# UBC-Thunderbots_PCB_Power__archive_power.net
KiCad netlist of a schematic drawn in Altium Designer
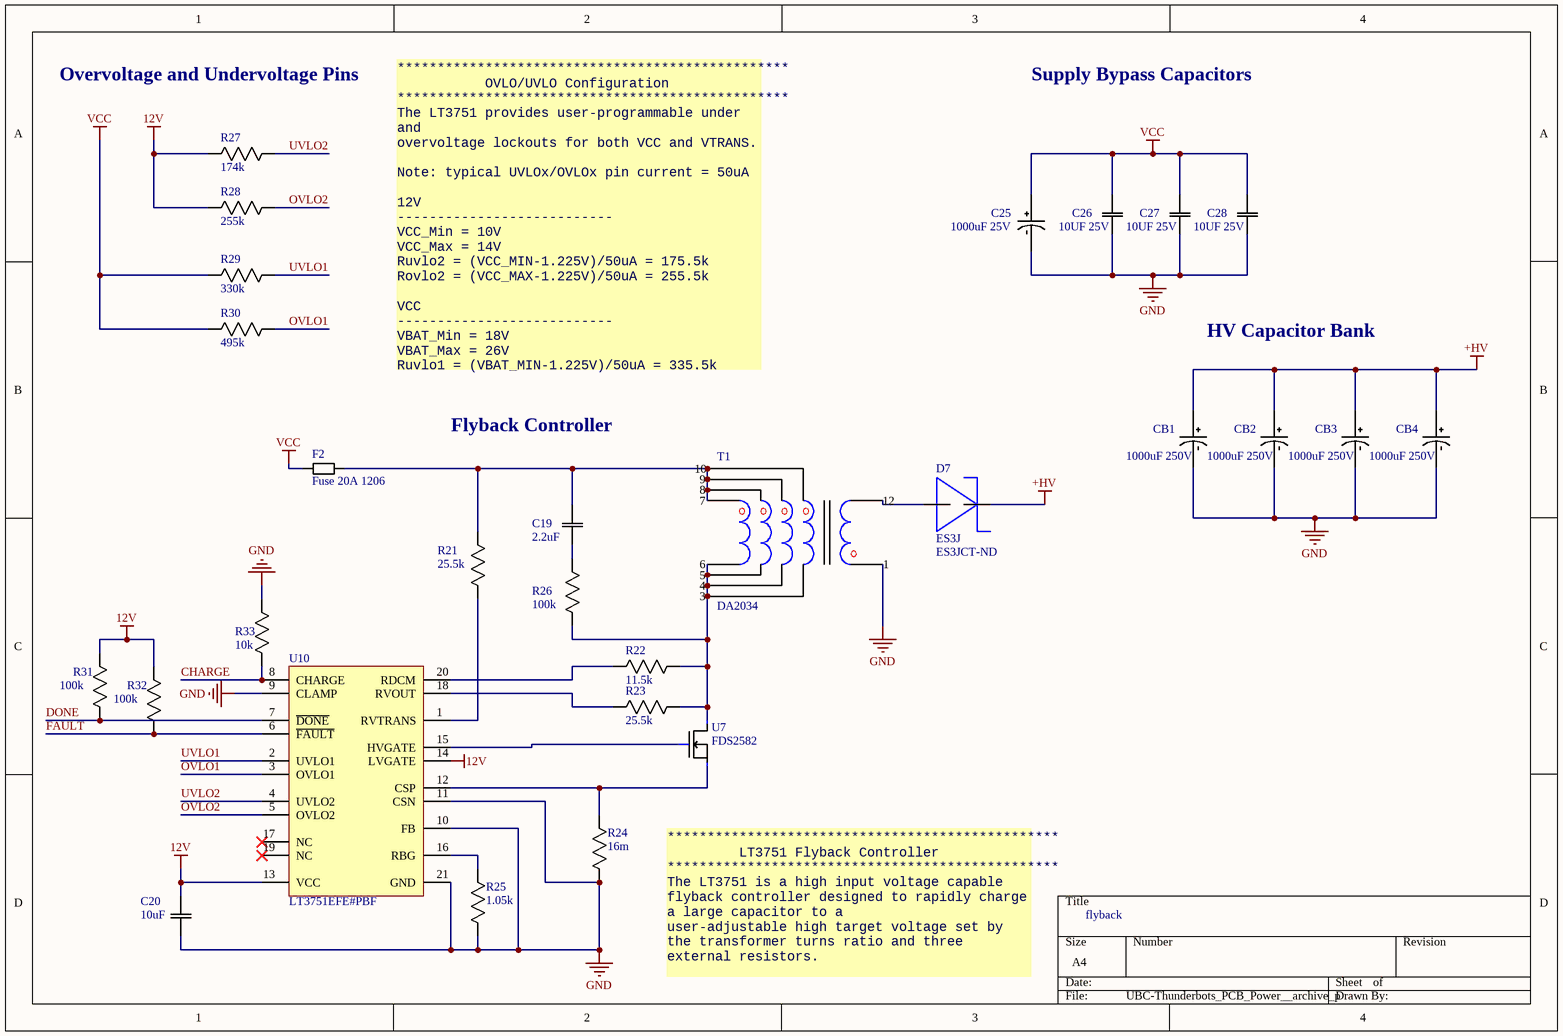
[diagram p0: UBC-Thunderbots_PCB_Power__archive_power-v2.2_pcb__flyback.SchDoc]

(export (version "E")
  (design (tool "Eeschema 10.0.6"))
  (components
    (comp (ref "C19")
      (value "2.2uF")
      (footprint "0805")
      (description "CAP CER 1UF 50V X7R 0805")
      (fields (field (name "MP") "C0805C225K4RACTU") (field (name "MF") "KEMET"))
      (libsource (lib "AltiumLibraries") (part "CAP 2.2uF 0805"))
    )
    (comp (ref "C20")
      (value "10uF")
      (footprint "0805")
      (description "CAP CER 10UF 10V X5R 0805")
      (fields (field (name "MP") "C0805C106K8PACTU") (field (name "MF") "KEMET"))
      (libsource (lib "AltiumLibraries") (part "CAP 10uF 0805"))
    )
    (comp (ref "C25")
      (value "1000uF 25V")
      (footprint "CAP POL 1000uF THRU")
      (description "NICHICON   UVR1E102MPD1TD   ALUMINUM ELECTROLYTIC CAPACITOR, 1000UF, 25V, 20%, RADIAL, FULL REEL")
      (fields
        (field (name "MANUFACTURER") "Nichicon")
        (field (name "MANUFACTURER PART NUMBER") "UVR1E102MPD1TD")
      )
      (libsource (lib "AltiumLibraries") (part "CAP POL 1000uF THRU"))
    )
    (comp (ref "C26")
      (value "10UF 25V")
      (footprint "1206")
      (description "CAP CER 10UF 25V X5R 1206")
      (fields (field (name "TOLERANCE") "10%"))
      (libsource (lib "") (part "CAP 10uF 25V_1"))
    )
    (comp (ref "C27")
      (value "10UF 25V")
      (footprint "1206")
      (description "CAP CER 10UF 25V X5R 1206")
      (fields (field (name "TOLERANCE") "10%"))
      (libsource (lib "AltiumLibraries") (part "CAP 10uF 25V"))
    )
    (comp (ref "C28")
      (value "10UF 25V")
      (footprint "1206")
      (description "CAP CER 10UF 25V X5R 1206")
      (fields (field (name "TOLERANCE") "10%"))
      (libsource (lib "AltiumLibraries") (part "CAP 10uF 25V"))
    )
    (comp (ref "CB1")
      (value "1000uF 250V")
      (description "1000µF 250V Aluminum Electrolytic Capacitors Radial, Can - Snap-In  3000 Hrs @ 85°C")
      (fields (field (name "TOLERANCE") "20%"))
      (libsource (lib "AltiumLibraries") (part "CAP ALUM 1000UF 20% 250V SNAP"))
    )
    (comp (ref "CB2")
      (value "1000uF 250V")
      (description "1000µF 250V Aluminum Electrolytic Capacitors Radial, Can - Snap-In  3000 Hrs @ 85°C")
      (fields (field (name "TOLERANCE") "20%"))
      (libsource (lib "AltiumLibraries") (part "CAP ALUM 1000UF 20% 250V SNAP"))
    )
    (comp (ref "CB3")
      (value "1000uF 250V")
      (description "1000µF 250V Aluminum Electrolytic Capacitors Radial, Can - Snap-In  3000 Hrs @ 85°C")
      (fields (field (name "TOLERANCE") "20%"))
      (libsource (lib "AltiumLibraries") (part "CAP ALUM 1000UF 20% 250V SNAP"))
    )
    (comp (ref "CB4")
      (value "1000uF 250V")
      (description "1000µF 250V Aluminum Electrolytic Capacitors Radial, Can - Snap-In  3000 Hrs @ 85°C")
      (fields (field (name "TOLERANCE") "20%"))
      (libsource (lib "AltiumLibraries") (part "CAP ALUM 1000UF 20% 250V SNAP"))
    )
    (comp (ref "D7")
      (value "ES3J")
      (footprint "D0214-AB")
      (description "Diode Switching 600V 3A 2-Pin DO-214AB T/R")
      (fields
        (field (name "MANUFACTURER") "ON Semiconductor / Fairchild")
        (field (name "VOLTAGE") "600V")
        (field (name "SUPPLIER PART NUMBER 1") "ES3JCT-ND")
      )
      (libsource (lib "AltiumLibraries") (part "ES3J"))
    )
    (comp (ref "F2")
      (value "Fuse 20A 1206")
      (footprint "1206")
      (description "FUSE 20A 32V AC 63V DC 1206")
      (libsource (lib "AltiumLibraries") (part "FUSE 20A 63V SLOW"))
    )
    (comp (ref "R21")
      (value "25.5k")
      (footprint "0805")
      (description "0805 Resistor, 6A, 0.125W, 25ppm, 0.1%, 25K5")
      (fields
        (field (name "MANUFACTURER") "Panasonic")
        (field (name "MANUFACTURER PART NUMBER") "ERA-6AEB2552V")
      )
      (libsource (lib "AltiumLibraries") (part "RES 25.5k 0805"))
    )
    (comp (ref "R22")
      (value "11.5k")
      (footprint "0805")
      (description "Res Thin Film 0805 11.5K Ohm 0.1% 1/8W 25ppm/C Molded SMD SMD Punched Carrier T/R")
      (fields
        (field (name "MANUFACTURER") "Panasonic")
        (field (name "MANUFACTURER PART NUMBER") "ERA-6AEB1152V")
      )
      (libsource (lib "AltiumLibraries") (part "RES 11.5k 0805"))
    )
    (comp (ref "R23")
      (value "25.5k")
      (footprint "0805")
      (description "0805 Resistor, 6A, 0.125W, 25ppm, 0.1%, 25K5")
      (fields
        (field (name "MANUFACTURER") "Panasonic")
        (field (name "MANUFACTURER PART NUMBER") "ERA-6AEB2552V")
      )
      (libsource (lib "") (part "RES 25.5k 0805_1"))
    )
    (comp (ref "R24")
      (value "16m")
      (footprint "0805")
      (description "Res Thick Film 0805 0.016 Ohm 1% 0.5W(1/2W) ±200ppm/C Molded SMD Automotive Punched T/R")
      (fields
        (field (name "MANUFACTURER") "Panasonic")
        (field (name "MANUFACTURER PART NUMBER") "ERJ-6BWFR016V")
      )
      (libsource (lib "AltiumLibraries") (part "RES 16mOhm 0805"))
    )
    (comp (ref "R25")
      (value "1.05k")
      (footprint "0805")
      (description "Res Thin Film 0805 10.5K Ohm 0.1% 0.125W(1/8W) ±25ppm/C Molded SMD Automotive Punched T/R")
      (fields
        (field (name "MANUFACTURER") "Panasonic")
        (field (name "MANUFACTURER PART NUMBER") "ERA-6AEB1052V")
      )
      (libsource (lib "AltiumLibraries") (part "RES 1.05k 0805"))
    )
    (comp (ref "R26")
      (value "100k")
      (footprint "0805")
      (description "RES SMD 100K OHM 1% 1/8W 0805")
      (fields (field (name "MP") "RC0805FR-07100KL") (field (name "MF") "Yageo"))
      (libsource (lib "AltiumLibraries") (part "RES 100k 0805"))
    )
    (comp (ref "R27")
      (value "174k")
      (footprint "0805")
      (description "RES SMD 174K OHM 1% 1/8W 0805")
      (fields
        (field (name "MANUFACTURER") "Yageo")
        (field (name "MANUFACTURER PART NUMBER") "RC0805FR-07174KL")
      )
      (libsource (lib "AltiumLibraries") (part "RES 174k 0805"))
    )
    (comp (ref "R28")
      (value "255k")
      (footprint "0805")
      (description "0805 Resistor, 6A, 0.125W, 25ppm, 0.1%, 255K")
      (fields
        (field (name "MANUFACTURER") "Panasonic")
        (field (name "MANUFACTURER PART NUMBER") "ERA-6AEB2553V")
      )
      (libsource (lib "AltiumLibraries") (part "RES 255k 0805"))
    )
    (comp (ref "R29")
      (value "330k")
      (footprint "0805")
      (description "RES SMD 274K OHM 1% 1/8W 0805")
      (libsource (lib "AltiumLibraries") (part "RES 330k 0805"))
    )
    (comp (ref "R30")
      (value "495k")
      (footprint "0805")
      (description "RES SMD 499K OHM 1% 1/8W 0805")
      (fields
        (field (name "MANUFACTURER") "Yageo")
        (field (name "MANUFACTURER PART NUMBER") "RC0805FR-07499KL")
      )
      (libsource (lib "AltiumLibraries") (part "RES 495k 0805"))
    )
    (comp (ref "R31")
      (value "100k")
      (footprint "0805")
      (description "RES SMD 100K OHM 1% 1/8W 0805")
      (fields (field (name "MP") "RC0805FR-07100KL") (field (name "MF") "Yageo"))
      (libsource (lib "") (part "RES 100k 0805_1"))
    )
    (comp (ref "R32")
      (value "100k")
      (footprint "0805")
      (description "RES SMD 100K OHM 1% 1/8W 0805")
      (fields (field (name "MP") "RC0805FR-07100KL") (field (name "MF") "Yageo"))
      (libsource (lib "") (part "RES 100k 0805_1"))
    )
    (comp (ref "R33")
      (value "10k")
      (footprint "0805")
      (description "RES SMD 10K OHM 1% 1/8W 0805")
      (fields (field (name "TOLERANCE") "1%"))
      (libsource (lib "AltiumLibraries") (part "RES 10k 1/8W"))
    )
    (comp (ref "T1")
      (value "DA2034")
      (footprint "DA2034")
      (description "Audio Transformers / Signal Transformers DA2032 Cap Chrgr For Linear LT3750/51")
      (libsource (lib "AltiumLibraries") (part "DA2034"))
    )
    (comp (ref "U7")
      (value "FDS2582")
      (footprint "8-SOIC MOSFET")
      (description "N-Channel 150V 4.1A (Ta) 2.5W (Ta) Surface Mount 8-SOIC")
      (fields (field (name "MF") "ON Semiconductor"))
      (libsource (lib "AltiumLibraries") (part "FDS2582"))
    )
    (comp (ref "U10")
      (value "LT3751EFE#PBF")
      (footprint "LT-FE-20-EPV-CB_L")
      (description "Controller to 20-Pin TSSOP EP")
      (fields (field (name "MANUFACTURER") "Analog Devices / Linear Technology"))
      (libsource (lib "AltiumLibraries") (part "LT3751EFE#PBF"))
    )
  )
  (nets
    (net (code "1") (name "+HV") (class "Default")
      (node (ref "CB1") (pin "POS") (pinfunction "POS_POS") (pintype "passive"))
      (node (ref "CB2") (pin "POS") (pinfunction "POS_POS") (pintype "passive"))
      (node (ref "CB3") (pin "POS") (pinfunction "POS_POS") (pintype "passive"))
      (node (ref "CB4") (pin "POS") (pinfunction "POS_POS") (pintype "passive"))
      (node (ref "D7") (pin "OUT") (pinfunction "OUT_OUT") (pintype "passive"))
    )
    (net (code "2") (name "/CHARGE") (class "Default")
      (node (ref "R33") (pin "2") (pinfunction "R2_2") (pintype "passive"))
      (node (ref "U10") (pin "8") (pinfunction "CHARGE_8") (pintype "passive"))
    )
    (net (code "3") (name "/DONE") (class "Default")
      (node (ref "R31") (pin "1") (pinfunction "R1_1") (pintype "passive"))
      (node (ref "U10") (pin "7") (pinfunction "~{DONE}_7") (pintype "passive"))
    )
    (net (code "4") (name "/FAULT") (class "Default")
      (node (ref "R32") (pin "1") (pinfunction "R1_1") (pintype "passive"))
      (node (ref "U10") (pin "6") (pinfunction "~{FAULT}_6") (pintype "passive"))
    )
    (net (code "5") (name "/OVLO1") (class "Default")
      (node (ref "R30") (pin "1") (pinfunction "R1_1") (pintype "passive"))
      (node (ref "U10") (pin "3") (pinfunction "OVLO1_3") (pintype "passive"))
    )
    (net (code "6") (name "/OVLO2") (class "Default")
      (node (ref "R28") (pin "1") (pinfunction "R1_1") (pintype "passive"))
      (node (ref "U10") (pin "5") (pinfunction "OVLO2_5") (pintype "passive"))
    )
    (net (code "7") (name "/UVLO1") (class "Default")
      (node (ref "R29") (pin "1") (pinfunction "R1_1") (pintype "passive"))
      (node (ref "U10") (pin "2") (pinfunction "UVLO1_2") (pintype "passive"))
    )
    (net (code "8") (name "/UVLO2") (class "Default")
      (node (ref "R27") (pin "1") (pinfunction "R1_1") (pintype "passive"))
      (node (ref "U10") (pin "4") (pinfunction "UVLO2_4") (pintype "passive"))
    )
    (net (code "9") (name "12V") (class "Default")
      (node (ref "C20") (pin "1") (pinfunction "C1_1") (pintype "passive"))
      (node (ref "R27") (pin "2") (pinfunction "R2_2") (pintype "passive"))
      (node (ref "R28") (pin "2") (pinfunction "R2_2") (pintype "passive"))
      (node (ref "R31") (pin "2") (pinfunction "R2_2") (pintype "passive"))
      (node (ref "R32") (pin "2") (pinfunction "R2_2") (pintype "passive"))
      (node (ref "U10") (pin "13") (pinfunction "VCC_13") (pintype "passive"))
      (node (ref "U10") (pin "14") (pinfunction "LVGATE_14") (pintype "passive"))
    )
    (net (code "10") (name "GND") (class "Default")
      (node (ref "C20") (pin "2") (pinfunction "C2_2") (pintype "passive"))
      (node (ref "C25") (pin "NEG") (pinfunction "NEG_NEG") (pintype "passive"))
      (node (ref "C26") (pin "1") (pinfunction "C1_1") (pintype "passive"))
      (node (ref "C27") (pin "1") (pinfunction "C1_1") (pintype "passive"))
      (node (ref "C28") (pin "1") (pinfunction "C1_1") (pintype "passive"))
      (node (ref "CB1") (pin "NEG") (pinfunction "NEG_NEG") (pintype "passive"))
      (node (ref "CB2") (pin "NEG") (pinfunction "NEG_NEG") (pintype "passive"))
      (node (ref "CB3") (pin "NEG") (pinfunction "NEG_NEG") (pintype "passive"))
      (node (ref "CB4") (pin "NEG") (pinfunction "NEG_NEG") (pintype "passive"))
      (node (ref "R24") (pin "2") (pinfunction "R2_2") (pintype "passive"))
      (node (ref "R25") (pin "2") (pinfunction "R2_2") (pintype "passive"))
      (node (ref "R33") (pin "1") (pinfunction "R1_1") (pintype "passive"))
      (node (ref "T1") (pin "1") (pinfunction "1_1") (pintype "passive"))
      (node (ref "U10") (pin "10") (pinfunction "FB_10") (pintype "passive"))
      (node (ref "U10") (pin "11") (pinfunction "CSN_11") (pintype "passive"))
      (node (ref "U10") (pin "21") (pinfunction "GND_21") (pintype "passive"))
      (node (ref "U10") (pin "9") (pinfunction "CLAMP_9") (pintype "passive"))
    )
    (net (code "11") (name "Net-(C19-C1)") (class "Default")
      (node (ref "C19") (pin "1") (pinfunction "C1_1") (pintype "passive"))
      (node (ref "R26") (pin "1") (pinfunction "R1_1") (pintype "passive"))
    )
    (net (code "12") (name "Net-(C19-C2)") (class "Default")
      (node (ref "C19") (pin "2") (pinfunction "C2_2") (pintype "passive"))
      (node (ref "F2") (pin "2") (pinfunction "2_2") (pintype "passive"))
      (node (ref "R21") (pin "1") (pinfunction "R1_1") (pintype "passive"))
      (node (ref "T1") (pin "10") (pinfunction "10_10") (pintype "passive"))
      (node (ref "T1") (pin "7") (pinfunction "7_7") (pintype "passive"))
      (node (ref "T1") (pin "8") (pinfunction "8_8") (pintype "passive"))
      (node (ref "T1") (pin "9") (pinfunction "9_9") (pintype "passive"))
    )
    (net (code "13") (name "Net-(D7-PadIN)") (class "Default")
      (node (ref "D7") (pin "IN") (pinfunction "IN_IN") (pintype "passive"))
      (node (ref "T1") (pin "12") (pinfunction "12_12") (pintype "passive"))
    )
    (net (code "14") (name "Net-(R21-R2)") (class "Default")
      (node (ref "R21") (pin "2") (pinfunction "R2_2") (pintype "passive"))
      (node (ref "U10") (pin "1") (pinfunction "RVTRANS_1") (pintype "passive"))
    )
    (net (code "15") (name "Net-(R22-R1)") (class "Default")
      (node (ref "R22") (pin "1") (pinfunction "R1_1") (pintype "passive"))
      (node (ref "R23") (pin "1") (pinfunction "R1_1") (pintype "passive"))
      (node (ref "R26") (pin "2") (pinfunction "R2_2") (pintype "passive"))
      (node (ref "T1") (pin "3") (pinfunction "3_3") (pintype "passive"))
      (node (ref "T1") (pin "4") (pinfunction "4_4") (pintype "passive"))
      (node (ref "T1") (pin "5") (pinfunction "5_5") (pintype "passive"))
      (node (ref "T1") (pin "6") (pinfunction "6_6") (pintype "passive"))
      (node (ref "U7") (pin "D") (pinfunction "D_D") (pintype "passive"))
    )
    (net (code "16") (name "Net-(R22-R2)") (class "Default")
      (node (ref "R22") (pin "2") (pinfunction "R2_2") (pintype "passive"))
      (node (ref "U10") (pin "20") (pinfunction "RDCM_20") (pintype "passive"))
    )
    (net (code "17") (name "Net-(R23-R2)") (class "Default")
      (node (ref "R23") (pin "2") (pinfunction "R2_2") (pintype "passive"))
      (node (ref "U10") (pin "18") (pinfunction "RVOUT_18") (pintype "passive"))
    )
    (net (code "18") (name "Net-(R24-R1)") (class "Default")
      (node (ref "R24") (pin "1") (pinfunction "R1_1") (pintype "passive"))
      (node (ref "U10") (pin "12") (pinfunction "CSP_12") (pintype "passive"))
      (node (ref "U7") (pin "S") (pinfunction "S_S") (pintype "passive"))
    )
    (net (code "19") (name "Net-(R25-R1)") (class "Default")
      (node (ref "R25") (pin "1") (pinfunction "R1_1") (pintype "passive"))
      (node (ref "U10") (pin "16") (pinfunction "RBG_16") (pintype "passive"))
    )
    (net (code "20") (name "Net-(U10-HVGATE)") (class "Default")
      (node (ref "U10") (pin "15") (pinfunction "HVGATE_15") (pintype "passive"))
      (node (ref "U7") (pin "G") (pinfunction "G_G") (pintype "passive"))
    )
    (net (code "21") (name "VCC") (class "Default")
      (node (ref "C25") (pin "POS") (pinfunction "POS_POS") (pintype "passive"))
      (node (ref "C26") (pin "2") (pinfunction "C2_2") (pintype "passive"))
      (node (ref "C27") (pin "2") (pinfunction "C2_2") (pintype "passive"))
      (node (ref "C28") (pin "2") (pinfunction "C2_2") (pintype "passive"))
      (node (ref "F2") (pin "1") (pinfunction "1_1") (pintype "passive"))
      (node (ref "R29") (pin "2") (pinfunction "R2_2") (pintype "passive"))
      (node (ref "R30") (pin "2") (pinfunction "R2_2") (pintype "passive"))
    )
    (net (code "22") (name "unconnected-(U10-NC-Pad17)") (class "Default")
      (node (ref "U10") (pin "17") (pinfunction "NC_17") (pintype "passive+no_connect"))
    )
    (net (code "23") (name "unconnected-(U10-NC-Pad19)") (class "Default")
      (node (ref "U10") (pin "19") (pinfunction "NC_19") (pintype "passive+no_connect"))
    )
  )
)
